# Splitter_aile_V1_schem.net
KiCad netlist of a schematic drawn in Altium Designer
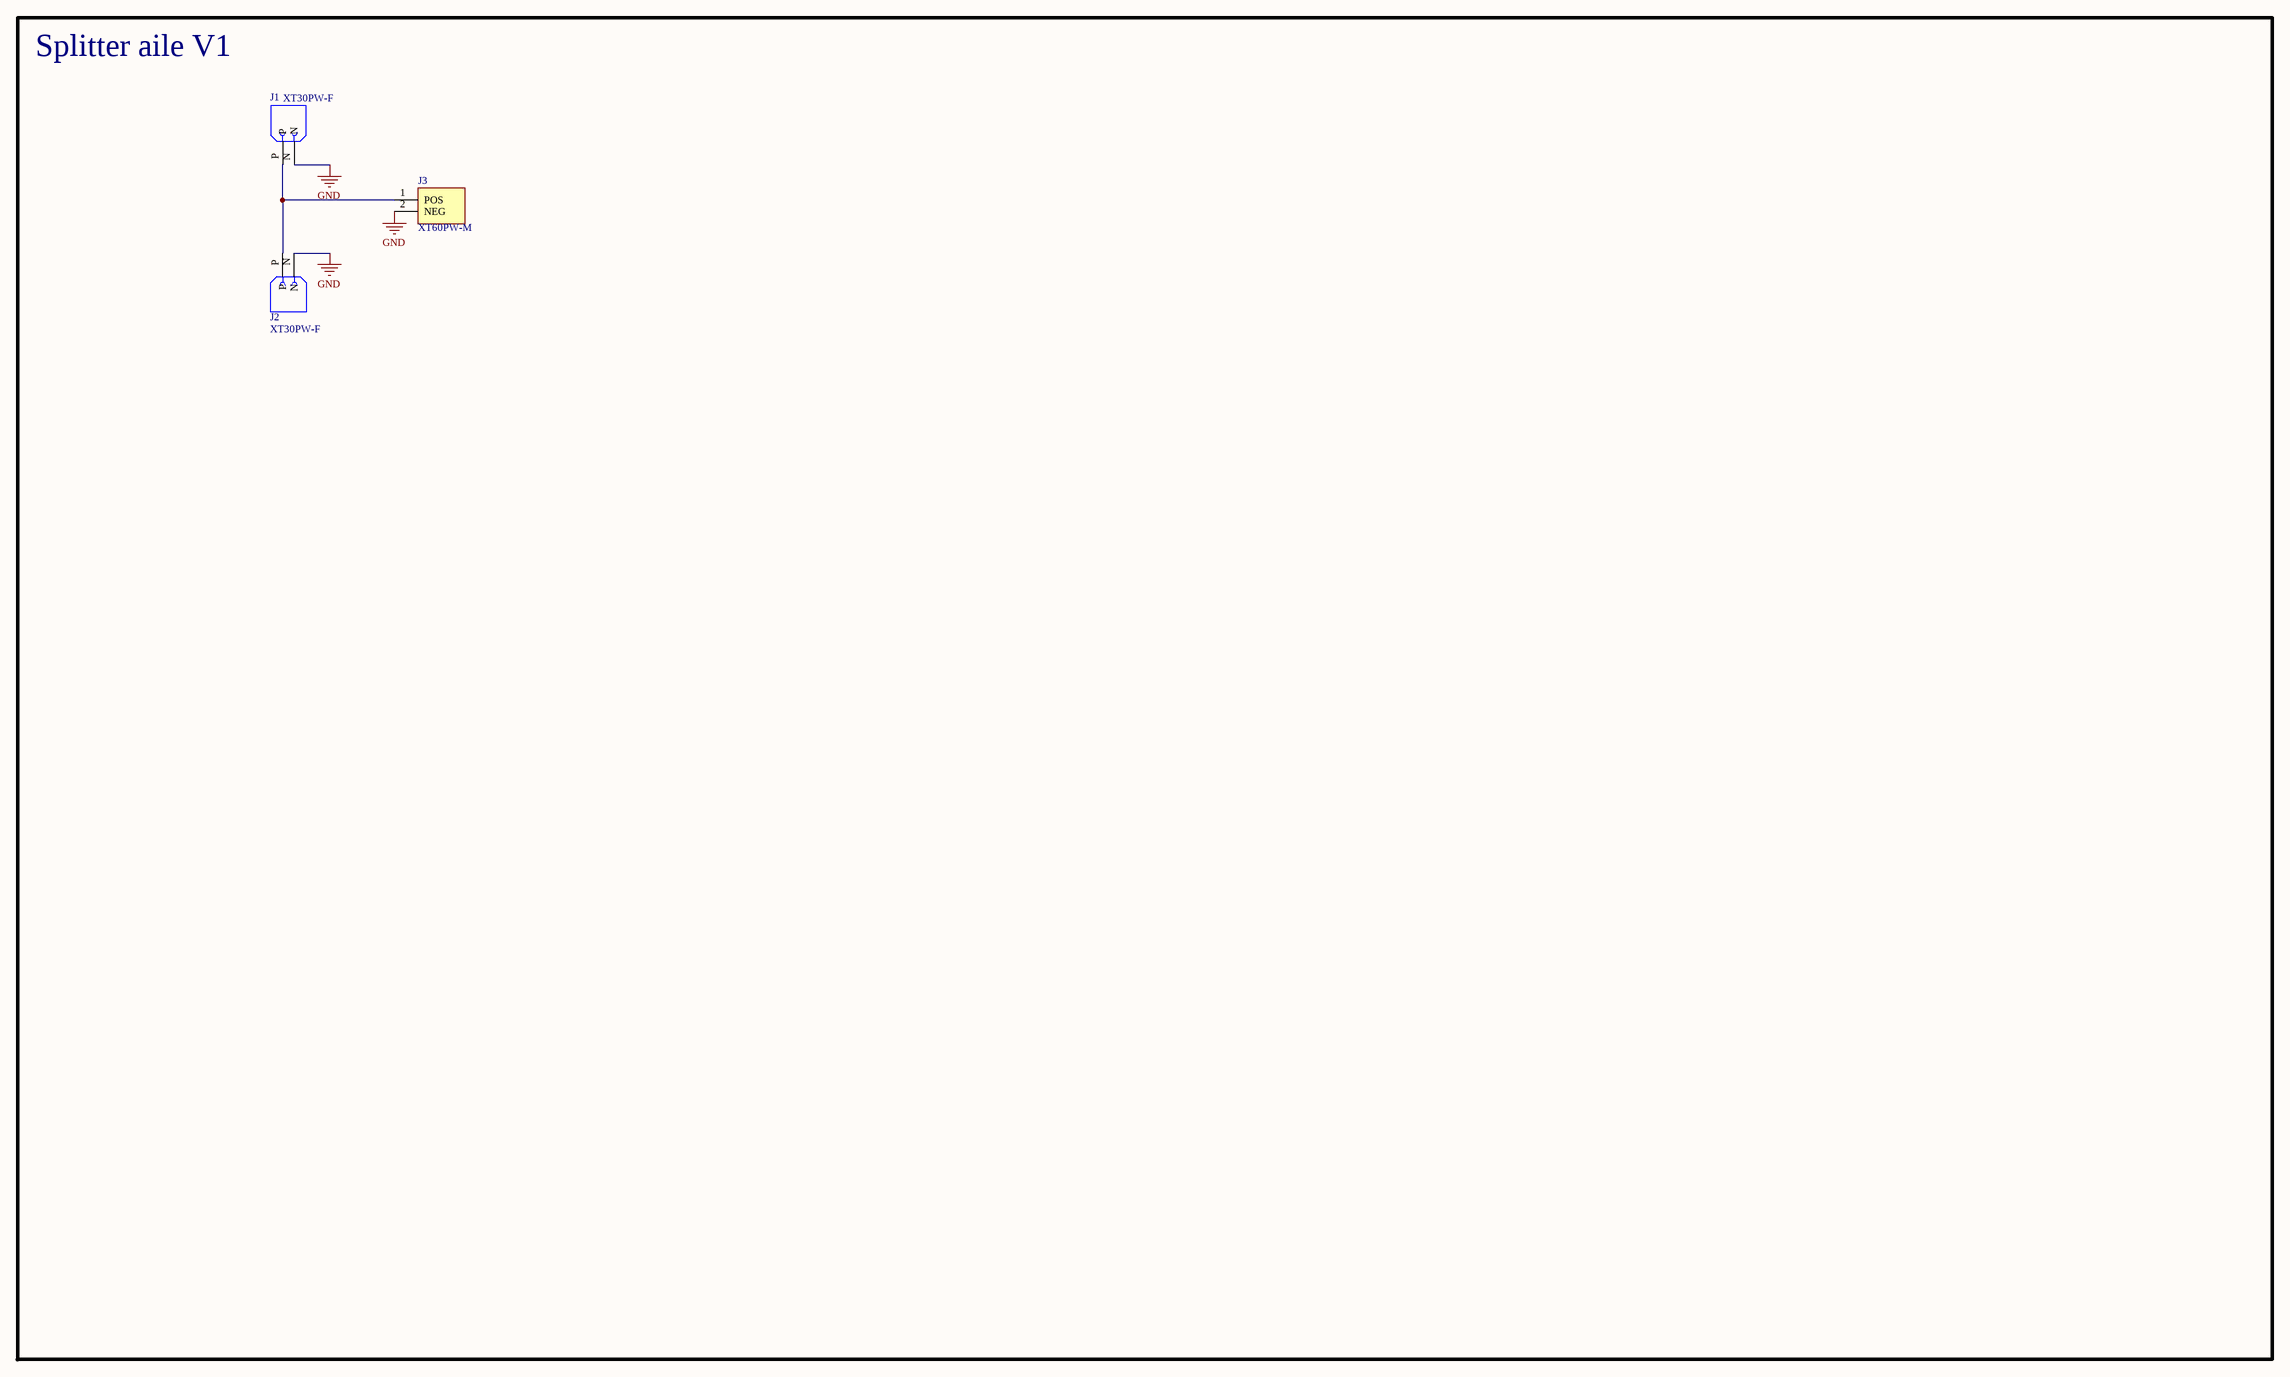
[diagram p0: Splitter_aile_V1_schem.SchDoc]

(export (version "E")
  (design (tool "Eeschema 10.0.6"))
  (components
    (comp (ref "J1")
      (value "XT30PW-F")
      (footprint "SamacSys:AMASS_XT30PW-F")
      (description "Socket; DC supply; XT30; female; PIN: 2; on PCBs; THT; yellow; 15A")
      (fields (field (name "MF") "amass"))
      (libsource (lib "SamacSys") (part "XT30PW-F"))
    )
    (comp (ref "J2")
      (value "XT30PW-F")
      (footprint "SamacSys:AMASS_XT30PW-F")
      (description "Socket; DC supply; XT30; female; PIN: 2; on PCBs; THT; yellow; 15A")
      (fields (field (name "MF") "amass"))
      (libsource (lib "") (part "XT30PW-F_1"))
    )
    (comp (ref "J3")
      (value "XT60PW-M")
      (footprint "SamacSys:AMASS_XT60PW-M")
      (description "Socket, DC supply, male, PIN: 2")
      (fields (field (name "MF") "AMASS"))
      (libsource (lib "SamacSys") (part "XT60PW-M"))
    )
  )
  (nets
    (net (code "1") (name "GND") (class "Default")
      (node (ref "J1") (pin "N") (pinfunction "N_N") (pintype "power_in"))
      (node (ref "J2") (pin "N") (pinfunction "N_N") (pintype "power_in"))
      (node (ref "J3") (pin "2") (pinfunction "NEG_2") (pintype "passive"))
    )
    (net (code "2") (name "Net-(J3-POS)") (class "Default")
      (node (ref "J1") (pin "P") (pinfunction "P_P") (pintype "power_in"))
      (node (ref "J2") (pin "P") (pinfunction "P_P") (pintype "power_in"))
      (node (ref "J3") (pin "1") (pinfunction "POS_1") (pintype "passive"))
    )
  )
)
